# Filter_Capacitors_-_Master_ICSP.net
KiCad netlist of a schematic drawn in Altium Designer
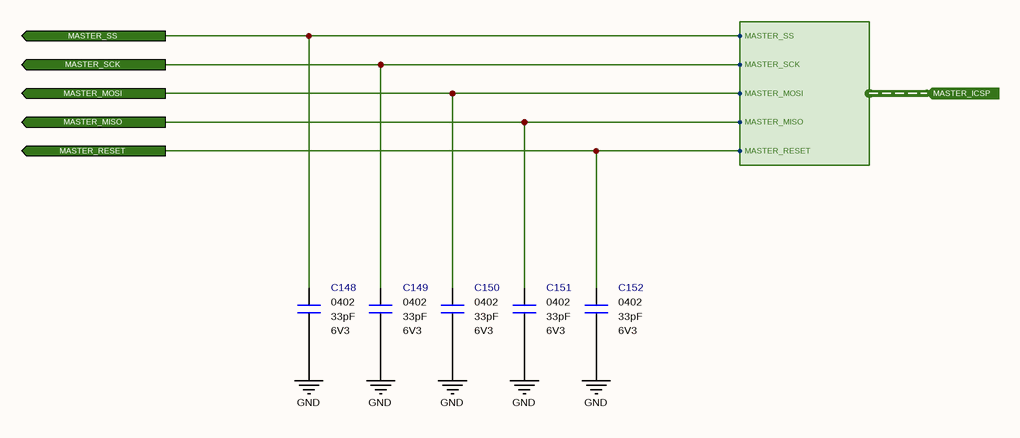
[diagram p0: Filter Capacitors - Master ICSP.SchDoc]

(export (version "E")
  (design (tool "Eeschema 10.0.6"))
  (components
    (comp (ref "C148")
      (value "33pF")
      (footprint "CAPACITOR_0402")
      (description "Capacitor - 33pF [0402] (Ceramic)")
      (fields
        (field (name "TOLERANCE") "10%")
        (field (name "CASE") "0402")
        (field (name "VOLTAGE") "6V3")
        (field (name "MANUFACTURER PART NUMBER") "C0402C330J9RACAUTO")
      )
      (libsource (lib "Ovoo_Library") (part "Capacitor - 33pF [0402-6V3]"))
    )
    (comp (ref "C149")
      (value "33pF")
      (footprint "CAPACITOR_0402")
      (description "Capacitor - 33pF [0402] (Ceramic)")
      (fields
        (field (name "TOLERANCE") "10%")
        (field (name "CASE") "0402")
        (field (name "VOLTAGE") "6V3")
        (field (name "MANUFACTURER PART NUMBER") "C0402C330J9RACAUTO")
      )
      (libsource (lib "Ovoo_Library") (part "Capacitor - 33pF [0402-6V3]"))
    )
    (comp (ref "C150")
      (value "33pF")
      (footprint "CAPACITOR_0402")
      (description "Capacitor - 33pF [0402] (Ceramic)")
      (fields
        (field (name "TOLERANCE") "10%")
        (field (name "CASE") "0402")
        (field (name "VOLTAGE") "6V3")
        (field (name "MANUFACTURER PART NUMBER") "C0402C330J9RACAUTO")
      )
      (libsource (lib "Ovoo_Library") (part "Capacitor - 33pF [0402-6V3]"))
    )
    (comp (ref "C151")
      (value "33pF")
      (footprint "CAPACITOR_0402")
      (description "Capacitor - 33pF [0402] (Ceramic)")
      (fields
        (field (name "TOLERANCE") "10%")
        (field (name "CASE") "0402")
        (field (name "VOLTAGE") "6V3")
        (field (name "MANUFACTURER PART NUMBER") "C0402C330J9RACAUTO")
      )
      (libsource (lib "Ovoo_Library") (part "Capacitor - 33pF [0402-6V3]"))
    )
    (comp (ref "C152")
      (value "33pF")
      (footprint "CAPACITOR_0402")
      (description "Capacitor - 33pF [0402] (Ceramic)")
      (fields
        (field (name "TOLERANCE") "10%")
        (field (name "CASE") "0402")
        (field (name "VOLTAGE") "6V3")
        (field (name "MANUFACTURER PART NUMBER") "C0402C330J9RACAUTO")
      )
      (libsource (lib "Ovoo_Library") (part "Capacitor - 33pF [0402-6V3]"))
    )
  )
  (nets
    (net (code "2") (name "/MASTER_MISO") (class "Default")
      (node (ref "C151") (pin "2") (pinfunction "2_2") (pintype "passive"))
    )
    (net (code "3") (name "/MASTER_MOSI") (class "Default")
      (node (ref "C150") (pin "2") (pinfunction "2_2") (pintype "passive"))
    )
    (net (code "4") (name "/MASTER_RESET") (class "Default")
      (node (ref "C152") (pin "2") (pinfunction "2_2") (pintype "passive"))
    )
    (net (code "5") (name "/MASTER_SCK") (class "Default")
      (node (ref "C149") (pin "2") (pinfunction "2_2") (pintype "passive"))
    )
    (net (code "6") (name "/MASTER_SS") (class "Default")
      (node (ref "C148") (pin "2") (pinfunction "2_2") (pintype "passive"))
    )
    (net (code "8") (name "GND") (class "Default")
      (node (ref "C148") (pin "1") (pinfunction "1_1") (pintype "passive"))
      (node (ref "C149") (pin "1") (pinfunction "1_1") (pintype "passive"))
      (node (ref "C150") (pin "1") (pinfunction "1_1") (pintype "passive"))
      (node (ref "C151") (pin "1") (pinfunction "1_1") (pintype "passive"))
      (node (ref "C152") (pin "1") (pinfunction "1_1") (pintype "passive"))
    )
  )
)
